# led-pcb.net
KiCad netlist of a schematic drawn in EAGLE
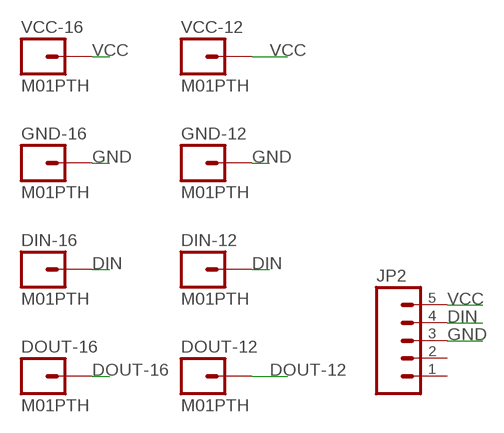
[diagram p0: schematic, sheet 1]

(export (version "E")
  (design (tool "Eeschema 10.0.6"))
  (components
    (comp (ref "DIN-12")
      (value "M01PTH")
      (footprint "eagle-import:1X01")
      (libsource (lib "eagle-import") (part "M01PTH"))
    )
    (comp (ref "DIN-16")
      (value "M01PTH")
      (footprint "eagle-import:1X01")
      (libsource (lib "eagle-import") (part "M01PTH"))
    )
    (comp (ref "DOUT-12")
      (value "M01PTH")
      (footprint "eagle-import:1X01")
      (libsource (lib "eagle-import") (part "M01PTH"))
    )
    (comp (ref "DOUT-16")
      (value "M01PTH")
      (footprint "eagle-import:1X01")
      (libsource (lib "eagle-import") (part "M01PTH"))
    )
    (comp (ref "GND-12")
      (value "M01PTH")
      (footprint "eagle-import:1X01")
      (libsource (lib "eagle-import") (part "M01PTH"))
    )
    (comp (ref "GND-16")
      (value "M01PTH")
      (footprint "eagle-import:1X01")
      (libsource (lib "eagle-import") (part "M01PTH"))
    )
    (comp (ref "JP2")
      (value "M05PTH")
      (footprint "eagle-import:1X05")
      (libsource (lib "eagle-import") (part "M05PTH"))
    )
    (comp (ref "VCC-12")
      (value "M01PTH")
      (footprint "eagle-import:1X01")
      (libsource (lib "eagle-import") (part "M01PTH"))
    )
    (comp (ref "VCC-16")
      (value "M01PTH")
      (footprint "eagle-import:1X01")
      (libsource (lib "eagle-import") (part "M01PTH"))
    )
  )
  (nets
    (net (code "1") (name "/DIN") (class "Default")
      (node (ref "DIN-12") (pin "1") (pinfunction "1_1") (pintype "passive"))
      (node (ref "DIN-16") (pin "1") (pinfunction "1_1") (pintype "passive"))
      (node (ref "JP2") (pin "4") (pinfunction "4_4") (pintype "passive"))
    )
    (net (code "2") (name "/DOUT-12") (class "Default")
      (node (ref "DOUT-12") (pin "1") (pinfunction "1_1") (pintype "passive"))
    )
    (net (code "3") (name "/DOUT-16") (class "Default")
      (node (ref "DOUT-16") (pin "1") (pinfunction "1_1") (pintype "passive"))
    )
    (net (code "4") (name "/GND") (class "Default")
      (node (ref "GND-12") (pin "1") (pinfunction "1_1") (pintype "passive"))
      (node (ref "GND-16") (pin "1") (pinfunction "1_1") (pintype "passive"))
      (node (ref "JP2") (pin "3") (pinfunction "3_3") (pintype "passive"))
    )
    (net (code "5") (name "/VCC") (class "Default")
      (node (ref "JP2") (pin "5") (pinfunction "5_5") (pintype "passive"))
      (node (ref "VCC-12") (pin "1") (pinfunction "1_1") (pintype "passive"))
      (node (ref "VCC-16") (pin "1") (pinfunction "1_1") (pintype "passive"))
    )
    (net (code "6") (name "unconnected-(JP2-Pad1)") (class "Default")
      (node (ref "JP2") (pin "1") (pinfunction "1_1") (pintype "passive"))
    )
    (net (code "7") (name "unconnected-(JP2-Pad2)") (class "Default")
      (node (ref "JP2") (pin "2") (pinfunction "2_2") (pintype "passive"))
    )
  )
)
